# EEPROM_Temp_LEDs.net
KiCad netlist of a schematic drawn in Altium Designer
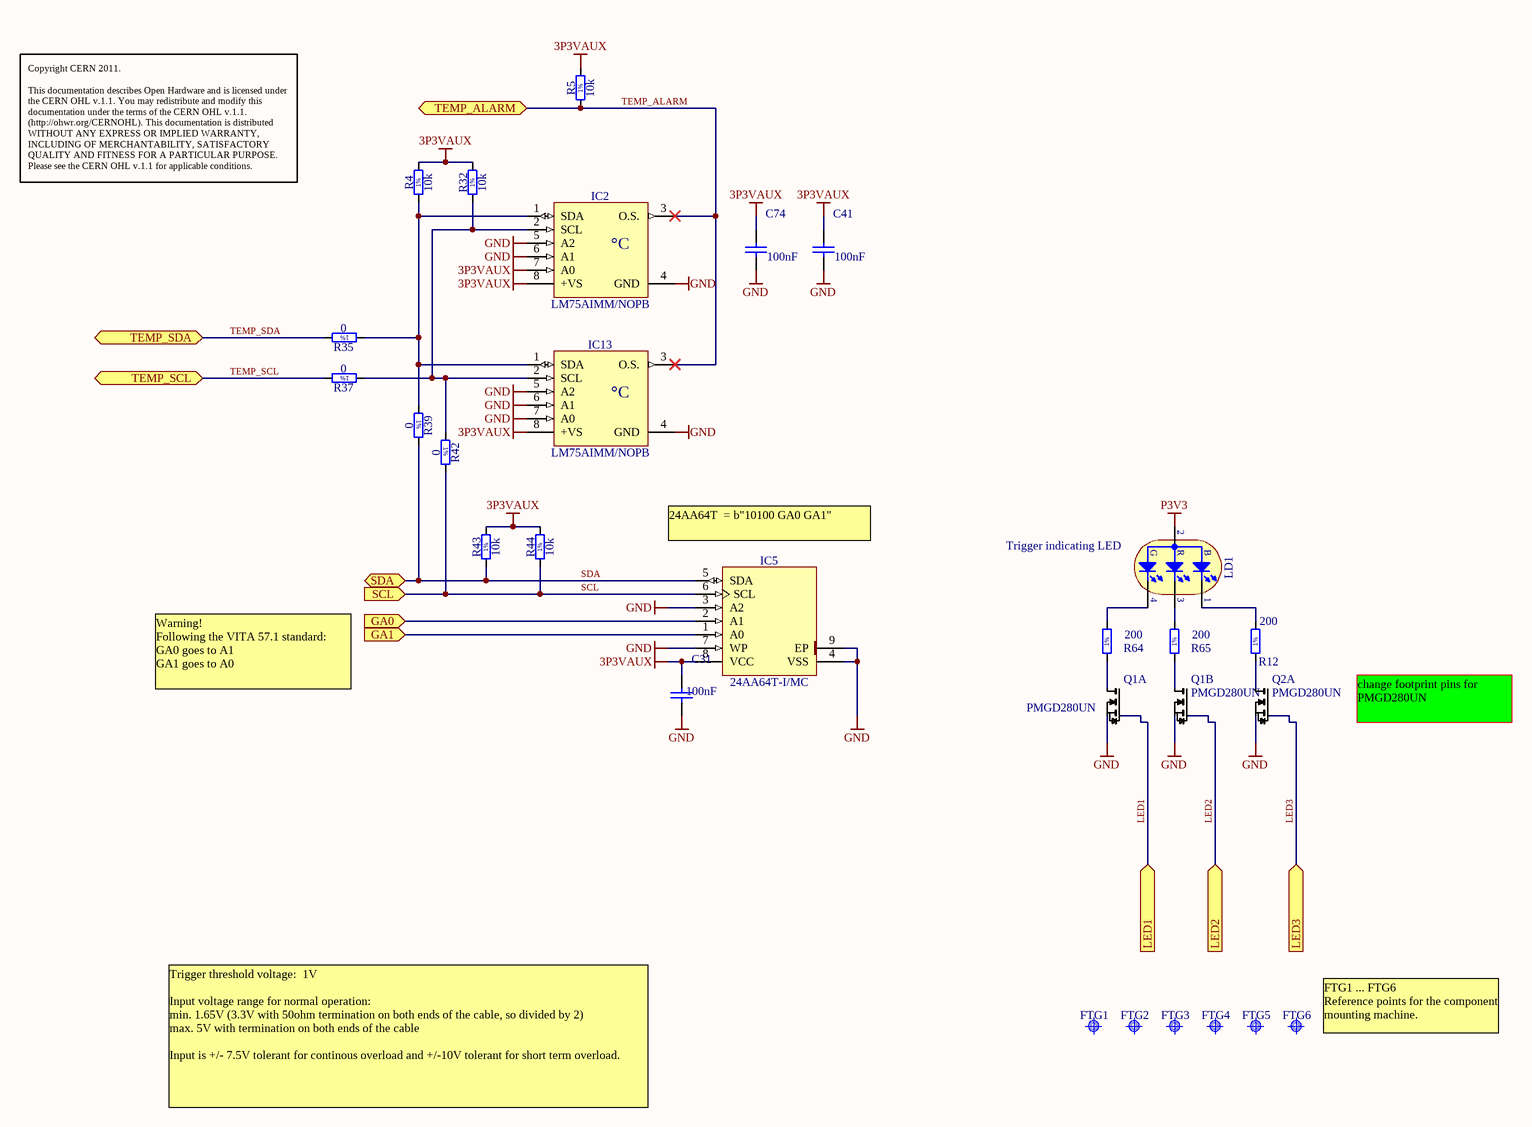
[diagram p0: EEPROM_Temp_LEDs.SchDoc]

(export (version "E")
  (design (tool "Eeschema 10.0.6"))
  (components
    (comp (ref "C31")
      (value "100nF")
      (footprint "CAPC0603X33N")
      (description "Non-polarised capacitor")
      (fields
        (field (name "PART NUMBER") "CC0201_100NF_6.3V_10%_X5R")
        (field (name "VOLTAGE") "6.3V")
        (field (name "AUTHOR") "CERN DEM JLC")
      )
      (libsource (lib "Capacitors") (part "Capacitor - non polarized"))
    )
    (comp (ref "C41")
      (value "100nF")
      (footprint "CAPC0603X33N")
      (description "Non-polarised capacitor")
      (fields
        (field (name "PART NUMBER") "CC0201_100NF_6.3V_10%_X5R")
        (field (name "VOLTAGE") "6.3V")
        (field (name "AUTHOR") "CERN DEM JLC")
      )
      (libsource (lib "Capacitors") (part "Capacitor - non polarized"))
    )
    (comp (ref "C74")
      (value "100nF")
      (footprint "CAPC0603X33N")
      (description "Non-polarised capacitor")
      (fields
        (field (name "PART NUMBER") "CC0201_100NF_6.3V_10%_X5R")
        (field (name "VOLTAGE") "6.3V")
        (field (name "AUTHOR") "CERN DEM JLC")
      )
      (libsource (lib "Capacitors") (part "Capacitor - non polarized"))
    )
    (comp (ref "FTG1")
      (value "Use only in PCB")
      (footprint "FIDUCIAL_TOP_S100-200")
      (description "Fiducial Target")
      (fields (field (name "PART NUMBER") "FIDUCIAL_TARGET_S100-200") (field (name "AUTHOR") "CERN DEM JLC"))
      (libsource (lib "Eletro-mechanical") (part "Fiducial Target"))
    )
    (comp (ref "FTG2")
      (value "Use only in PCB")
      (footprint "FIDUCIAL_TOP_S100-200")
      (description "Fiducial Target")
      (fields (field (name "PART NUMBER") "FIDUCIAL_TARGET_S100-200") (field (name "AUTHOR") "CERN DEM JLC"))
      (libsource (lib "Eletro-mechanical") (part "Fiducial Target"))
    )
    (comp (ref "FTG3")
      (value "Use only in PCB")
      (footprint "FIDUCIAL_TOP_S100-200")
      (description "Fiducial Target")
      (fields (field (name "PART NUMBER") "FIDUCIAL_TARGET_S100-200") (field (name "AUTHOR") "CERN DEM JLC"))
      (libsource (lib "Eletro-mechanical") (part "Fiducial Target"))
    )
    (comp (ref "FTG4")
      (value "Use only in PCB")
      (footprint "FIDUCIAL_TOP_S100-200")
      (description "Fiducial Target")
      (fields (field (name "PART NUMBER") "FIDUCIAL_TARGET_S100-200") (field (name "AUTHOR") "CERN DEM JLC"))
      (libsource (lib "Eletro-mechanical") (part "Fiducial Target"))
    )
    (comp (ref "FTG5")
      (value "Use only in PCB")
      (footprint "FIDUCIAL_TOP_S100-200")
      (description "Fiducial Target")
      (fields (field (name "PART NUMBER") "FIDUCIAL_TARGET_S100-200") (field (name "AUTHOR") "CERN DEM JLC"))
      (libsource (lib "Eletro-mechanical") (part "Fiducial Target"))
    )
    (comp (ref "FTG6")
      (value "Use only in PCB")
      (footprint "FIDUCIAL_TOP_S100-200")
      (description "Fiducial Target")
      (fields (field (name "PART NUMBER") "FIDUCIAL_TARGET_S100-200") (field (name "AUTHOR") "CERN DEM JLC"))
      (libsource (lib "Eletro-mechanical") (part "Fiducial Target"))
    )
    (comp (ref "IC2")
      (value "LM75AIMM/NOPB")
      (footprint "SOP65P490X109-8N")
      (description "Digital Temperature Sensor and Thermal Watchdog with Two-Wire Interface")
      (fields (field (name "MANUFACTURER") "TEXAS INSTRUMENTS") (field (name "AUTHOR") "CERN DEM JLC"))
      (libsource (lib "ICs And Semiconductors") (part "LM75"))
    )
    (comp (ref "IC5")
      (value "24AA64T-I/MC")
      (footprint "SON50P300X200X100-9N-S175X155")
      (description "1.7-5.5V 64K I2C Serial EEPROM")
      (fields (field (name "MANUFACTURER") "MICROCHIP TECHNOLOGY") (field (name "AUTHOR") "CERN DEM JLC"))
      (libsource (lib "ICs And Semiconductors") (part "24AA64T-I/MC"))
    )
    (comp (ref "IC13")
      (value "LM75AIMM/NOPB")
      (footprint "SOP65P490X109-8N")
      (description "Digital Temperature Sensor and Thermal Watchdog with Two-Wire Interface")
      (fields (field (name "MANUFACTURER") "TEXAS INSTRUMENTS") (field (name "AUTHOR") "CERN DEM JLC"))
      (libsource (lib "ICs And Semiconductors") (part "LM75"))
    )
    (comp (ref "LD1")
      (value "Blue/Red/Green")
      (footprint "LED_AVAGO_HSMF-C113")
      (description "Tricolor LEDs 1 Cathode Blue, 2 Common Anode, 3 Cathode Red, 4 Cathode Green")
      (fields
        (field (name "PART NUMBER") "LED_AVAGO_HSMF-C113")
        (field (name "MANUFACTURER") "AVAGO TECHNOLOGIES")
        (field (name "AUTHOR") "CERN DEM JLC")
      )
      (libsource (lib "ICs And Semiconductors") (part "LED Blue-Red-Green 1CB_2AC_3CR_4CG"))
    )
    (comp (ref "Q1")
      (value "PMGD280UN")
      (footprint "SOT-363")
      (description "Dual NMOS 20V,08.A, 340mR, Vt=0.7V")
      (libsource (lib "LIBRARY_SCH") (part "Q_PMGD280UN"))
    )
    (comp (ref "Q2")
      (value "PMGD280UN")
      (footprint "SOT-363")
      (description "Dual NMOS 20V,08.A, 340mR, Vt=0.7V")
      (libsource (lib "LIBRARY_SCH") (part "Q_PMGD280UN"))
    )
    (comp (ref "R4")
      (value "10k")
      (footprint "RESC1005X40N")
      (description "Resistor - 1%")
      (fields
        (field (name "PART NUMBER") "R0402_10K_1%_0.0625W_100PPM")
        (field (name "POWER") "0.0625W")
        (field (name "AUTHOR") "CERN DEM JLC")
      )
      (libsource (lib "Resistors") (part "Resistor - 1%"))
    )
    (comp (ref "R5")
      (value "10k")
      (footprint "RESC1005X40N")
      (description "Resistor - 1%")
      (fields
        (field (name "PART NUMBER") "R0402_10K_1%_0.0625W_100PPM")
        (field (name "POWER") "0.0625W")
        (field (name "AUTHOR") "CERN DEM JLC")
      )
      (libsource (lib "Resistors") (part "Resistor - 1%"))
    )
    (comp (ref "R12")
      (value "200")
      (footprint "RESC1005X40N")
      (description "Resistor - 1%")
      (fields
        (field (name "PART NUMBER") "R0402_200R_1%_0.0625W_100PPM")
        (field (name "POWER") "0.0625W")
        (field (name "AUTHOR") "CERN DEM JLC")
      )
      (libsource (lib "Resistors") (part "Resistor - 1%"))
    )
    (comp (ref "R32")
      (value "10k")
      (footprint "RESC1005X40N")
      (description "Resistor - 1%")
      (fields
        (field (name "PART NUMBER") "R0402_10K_1%_0.0625W_100PPM")
        (field (name "POWER") "0.0625W")
        (field (name "AUTHOR") "CERN DEM JLC")
      )
      (libsource (lib "Resistors") (part "Resistor - 1%"))
    )
    (comp (ref "R35")
      (value "0")
      (footprint "RESC1005X40N")
      (description "Resistor - 1%")
      (fields
        (field (name "PART NUMBER") "R0402_0R_JUMPER")
        (field (name "MANUFACTURER") "GENERIC")
        (field (name "AUTHOR") "CERN DEM JLC")
      )
      (libsource (lib "Resistors") (part "Resistor - 1%"))
    )
    (comp (ref "R37")
      (value "0")
      (footprint "RESC1005X40N")
      (description "Resistor - 1%")
      (fields
        (field (name "PART NUMBER") "R0402_0R_JUMPER")
        (field (name "MANUFACTURER") "GENERIC")
        (field (name "AUTHOR") "CERN DEM JLC")
      )
      (libsource (lib "Resistors") (part "Resistor - 1%"))
    )
    (comp (ref "R39")
      (value "0")
      (footprint "RESC1005X40N")
      (description "Resistor - 1%")
      (fields
        (field (name "PART NUMBER") "R0402_0R_JUMPER")
        (field (name "MANUFACTURER") "GENERIC")
        (field (name "AUTHOR") "CERN DEM JLC")
      )
      (libsource (lib "Resistors") (part "Resistor - 1%"))
    )
    (comp (ref "R42")
      (value "0")
      (footprint "RESC1005X40N")
      (description "Resistor - 1%")
      (fields
        (field (name "PART NUMBER") "R0402_0R_JUMPER")
        (field (name "MANUFACTURER") "GENERIC")
        (field (name "AUTHOR") "CERN DEM JLC")
      )
      (libsource (lib "Resistors") (part "Resistor - 1%"))
    )
    (comp (ref "R43")
      (value "10k")
      (footprint "RESC1005X40N")
      (description "Resistor - 1%")
      (fields
        (field (name "PART NUMBER") "R0402_10K_1%_0.0625W_100PPM")
        (field (name "POWER") "0.0625W")
        (field (name "AUTHOR") "CERN DEM JLC")
      )
      (libsource (lib "Resistors") (part "Resistor - 1%"))
    )
    (comp (ref "R44")
      (value "10k")
      (footprint "RESC1005X40N")
      (description "Resistor - 1%")
      (fields
        (field (name "PART NUMBER") "R0402_10K_1%_0.0625W_100PPM")
        (field (name "POWER") "0.0625W")
        (field (name "AUTHOR") "CERN DEM JLC")
      )
      (libsource (lib "Resistors") (part "Resistor - 1%"))
    )
    (comp (ref "R64")
      (value "200")
      (footprint "RESC1005X40N")
      (description "Resistor - 1%")
      (fields
        (field (name "PART NUMBER") "R0402_200R_1%_0.0625W_100PPM")
        (field (name "POWER") "0.0625W")
        (field (name "AUTHOR") "CERN DEM JLC")
      )
      (libsource (lib "Resistors") (part "Resistor - 1%"))
    )
    (comp (ref "R65")
      (value "200")
      (footprint "RESC1005X40N")
      (description "Resistor - 1%")
      (fields
        (field (name "PART NUMBER") "R0402_200R_1%_0.0625W_100PPM")
        (field (name "POWER") "0.0625W")
        (field (name "AUTHOR") "CERN DEM JLC")
      )
      (libsource (lib "Resistors") (part "Resistor - 1%"))
    )
  )
  (nets
    (net (code "1") (name "/GA0") (class "Default")
      (node (ref "IC5") (pin "2") (pinfunction "A1_2") (pintype "input"))
    )
    (net (code "2") (name "/GA1") (class "Default")
      (node (ref "IC5") (pin "1") (pinfunction "A0_1") (pintype "input"))
    )
    (net (code "3") (name "/LED1") (class "Default")
      (node (ref "Q1") (pin "2") (pinfunction "G1_2") (pintype "input"))
    )
    (net (code "4") (name "/LED2") (class "Default")
      (node (ref "Q1") (pin "5") (pinfunction "G2_5") (pintype "input"))
    )
    (net (code "5") (name "/LED3") (class "Default")
      (node (ref "Q2") (pin "2") (pinfunction "G1_2") (pintype "input"))
    )
    (net (code "6") (name "/SCL") (class "Default")
      (node (ref "IC5") (pin "6") (pinfunction "SCL_6") (pintype "input"))
      (node (ref "R42") (pin "2") (pinfunction "2_2") (pintype "passive"))
      (node (ref "R44") (pin "1") (pinfunction "1_1") (pintype "passive"))
    )
    (net (code "7") (name "/SDA") (class "Default")
      (node (ref "IC5") (pin "5") (pinfunction "SDA_5") (pintype "bidirectional"))
      (node (ref "R39") (pin "2") (pinfunction "2_2") (pintype "passive"))
      (node (ref "R43") (pin "1") (pinfunction "1_1") (pintype "passive"))
    )
    (net (code "8") (name "/TEMP_ALARM") (class "Default")
      (node (ref "IC13") (pin "3") (pinfunction "O.S._3") (pintype "output"))
      (node (ref "IC2") (pin "3") (pinfunction "O.S._3") (pintype "output"))
      (node (ref "R5") (pin "1") (pinfunction "1_1") (pintype "passive"))
    )
    (net (code "9") (name "/TEMP_SCL") (class "Default")
      (node (ref "R37") (pin "2") (pinfunction "2_2") (pintype "passive"))
    )
    (net (code "10") (name "/TEMP_SDA") (class "Default")
      (node (ref "R35") (pin "2") (pinfunction "2_2") (pintype "passive"))
    )
    (net (code "11") (name "3P3VAUX") (class "Default")
      (node (ref "C31") (pin "1") (pinfunction "1_1") (pintype "passive"))
      (node (ref "C41") (pin "1") (pinfunction "1_1") (pintype "passive"))
      (node (ref "C74") (pin "1") (pinfunction "1_1") (pintype "passive"))
      (node (ref "IC13") (pin "8") (pinfunction "+VS_8") (pintype "power_in"))
      (node (ref "IC2") (pin "7") (pinfunction "A0_7") (pintype "input"))
      (node (ref "IC2") (pin "8") (pinfunction "+VS_8") (pintype "power_in"))
      (node (ref "IC5") (pin "8") (pinfunction "VCC_8") (pintype "power_in"))
      (node (ref "R32") (pin "2") (pinfunction "2_2") (pintype "passive"))
      (node (ref "R4") (pin "2") (pinfunction "2_2") (pintype "passive"))
      (node (ref "R43") (pin "2") (pinfunction "2_2") (pintype "passive"))
      (node (ref "R44") (pin "2") (pinfunction "2_2") (pintype "passive"))
      (node (ref "R5") (pin "2") (pinfunction "2_2") (pintype "passive"))
    )
    (net (code "12") (name "GND") (class "Default")
      (node (ref "C31") (pin "2") (pinfunction "2_2") (pintype "passive"))
      (node (ref "C41") (pin "2") (pinfunction "2_2") (pintype "passive"))
      (node (ref "C74") (pin "2") (pinfunction "2_2") (pintype "passive"))
      (node (ref "IC13") (pin "4") (pinfunction "GND_4") (pintype "power_in"))
      (node (ref "IC13") (pin "5") (pinfunction "A2_5") (pintype "input"))
      (node (ref "IC13") (pin "6") (pinfunction "A1_6") (pintype "input"))
      (node (ref "IC13") (pin "7") (pinfunction "A0_7") (pintype "input"))
      (node (ref "IC2") (pin "4") (pinfunction "GND_4") (pintype "power_in"))
      (node (ref "IC2") (pin "5") (pinfunction "A2_5") (pintype "input"))
      (node (ref "IC2") (pin "6") (pinfunction "A1_6") (pintype "input"))
      (node (ref "IC5") (pin "3") (pinfunction "A2_3") (pintype "input"))
      (node (ref "IC5") (pin "4") (pinfunction "VSS_4") (pintype "power_in"))
      (node (ref "IC5") (pin "7") (pinfunction "WP_7") (pintype "input"))
      (node (ref "IC5") (pin "9") (pinfunction "EP_9") (pintype "power_in"))
      (node (ref "Q1") (pin "1") (pinfunction "S1_1") (pintype "open_emitter"))
      (node (ref "Q1") (pin "4") (pinfunction "S2_4") (pintype "open_emitter"))
      (node (ref "Q2") (pin "1") (pinfunction "S1_1") (pintype "open_emitter"))
    )
    (net (code "13") (name "Net-(IC13-SCL)") (class "Default")
      (node (ref "IC13") (pin "2") (pinfunction "SCL_2") (pintype "input"))
      (node (ref "IC2") (pin "2") (pinfunction "SCL_2") (pintype "input"))
      (node (ref "R32") (pin "1") (pinfunction "1_1") (pintype "passive"))
      (node (ref "R37") (pin "1") (pinfunction "1_1") (pintype "passive"))
      (node (ref "R42") (pin "1") (pinfunction "1_1") (pintype "passive"))
    )
    (net (code "14") (name "Net-(IC13-SDA)") (class "Default")
      (node (ref "IC13") (pin "1") (pinfunction "SDA_1") (pintype "bidirectional"))
      (node (ref "IC2") (pin "1") (pinfunction "SDA_1") (pintype "bidirectional"))
      (node (ref "R35") (pin "1") (pinfunction "1_1") (pintype "passive"))
      (node (ref "R39") (pin "1") (pinfunction "1_1") (pintype "passive"))
      (node (ref "R4") (pin "1") (pinfunction "1_1") (pintype "passive"))
    )
    (net (code "15") (name "Net-(LD1-CB)") (class "Default")
      (node (ref "LD1") (pin "1") (pinfunction "CB_1") (pintype "passive"))
      (node (ref "R12") (pin "2") (pinfunction "2_2") (pintype "passive"))
    )
    (net (code "16") (name "Net-(LD1-CG)") (class "Default")
      (node (ref "LD1") (pin "4") (pinfunction "CG_4") (pintype "passive"))
      (node (ref "R64") (pin "2") (pinfunction "2_2") (pintype "passive"))
    )
    (net (code "17") (name "Net-(LD1-CR)") (class "Default")
      (node (ref "LD1") (pin "3") (pinfunction "CR_3") (pintype "passive"))
      (node (ref "R65") (pin "2") (pinfunction "2_2") (pintype "passive"))
    )
    (net (code "18") (name "Net-(Q1A-D1)") (class "Default")
      (node (ref "Q1") (pin "6") (pinfunction "D1_6") (pintype "open_collector"))
      (node (ref "R64") (pin "1") (pinfunction "1_1") (pintype "passive"))
    )
    (net (code "19") (name "Net-(Q1B-D2)") (class "Default")
      (node (ref "Q1") (pin "3") (pinfunction "D2_3") (pintype "open_collector"))
      (node (ref "R65") (pin "1") (pinfunction "1_1") (pintype "passive"))
    )
    (net (code "20") (name "Net-(Q2A-D1)") (class "Default")
      (node (ref "Q2") (pin "6") (pinfunction "D1_6") (pintype "open_collector"))
      (node (ref "R12") (pin "1") (pinfunction "1_1") (pintype "passive"))
    )
    (net (code "21") (name "P3V3") (class "Default")
      (node (ref "LD1") (pin "2") (pinfunction "AC_2") (pintype "passive"))
    )
  )
)
